# SCH_LFOx3_2024-04-05.net
KiCad netlist of a schematic drawn in EasyEDA
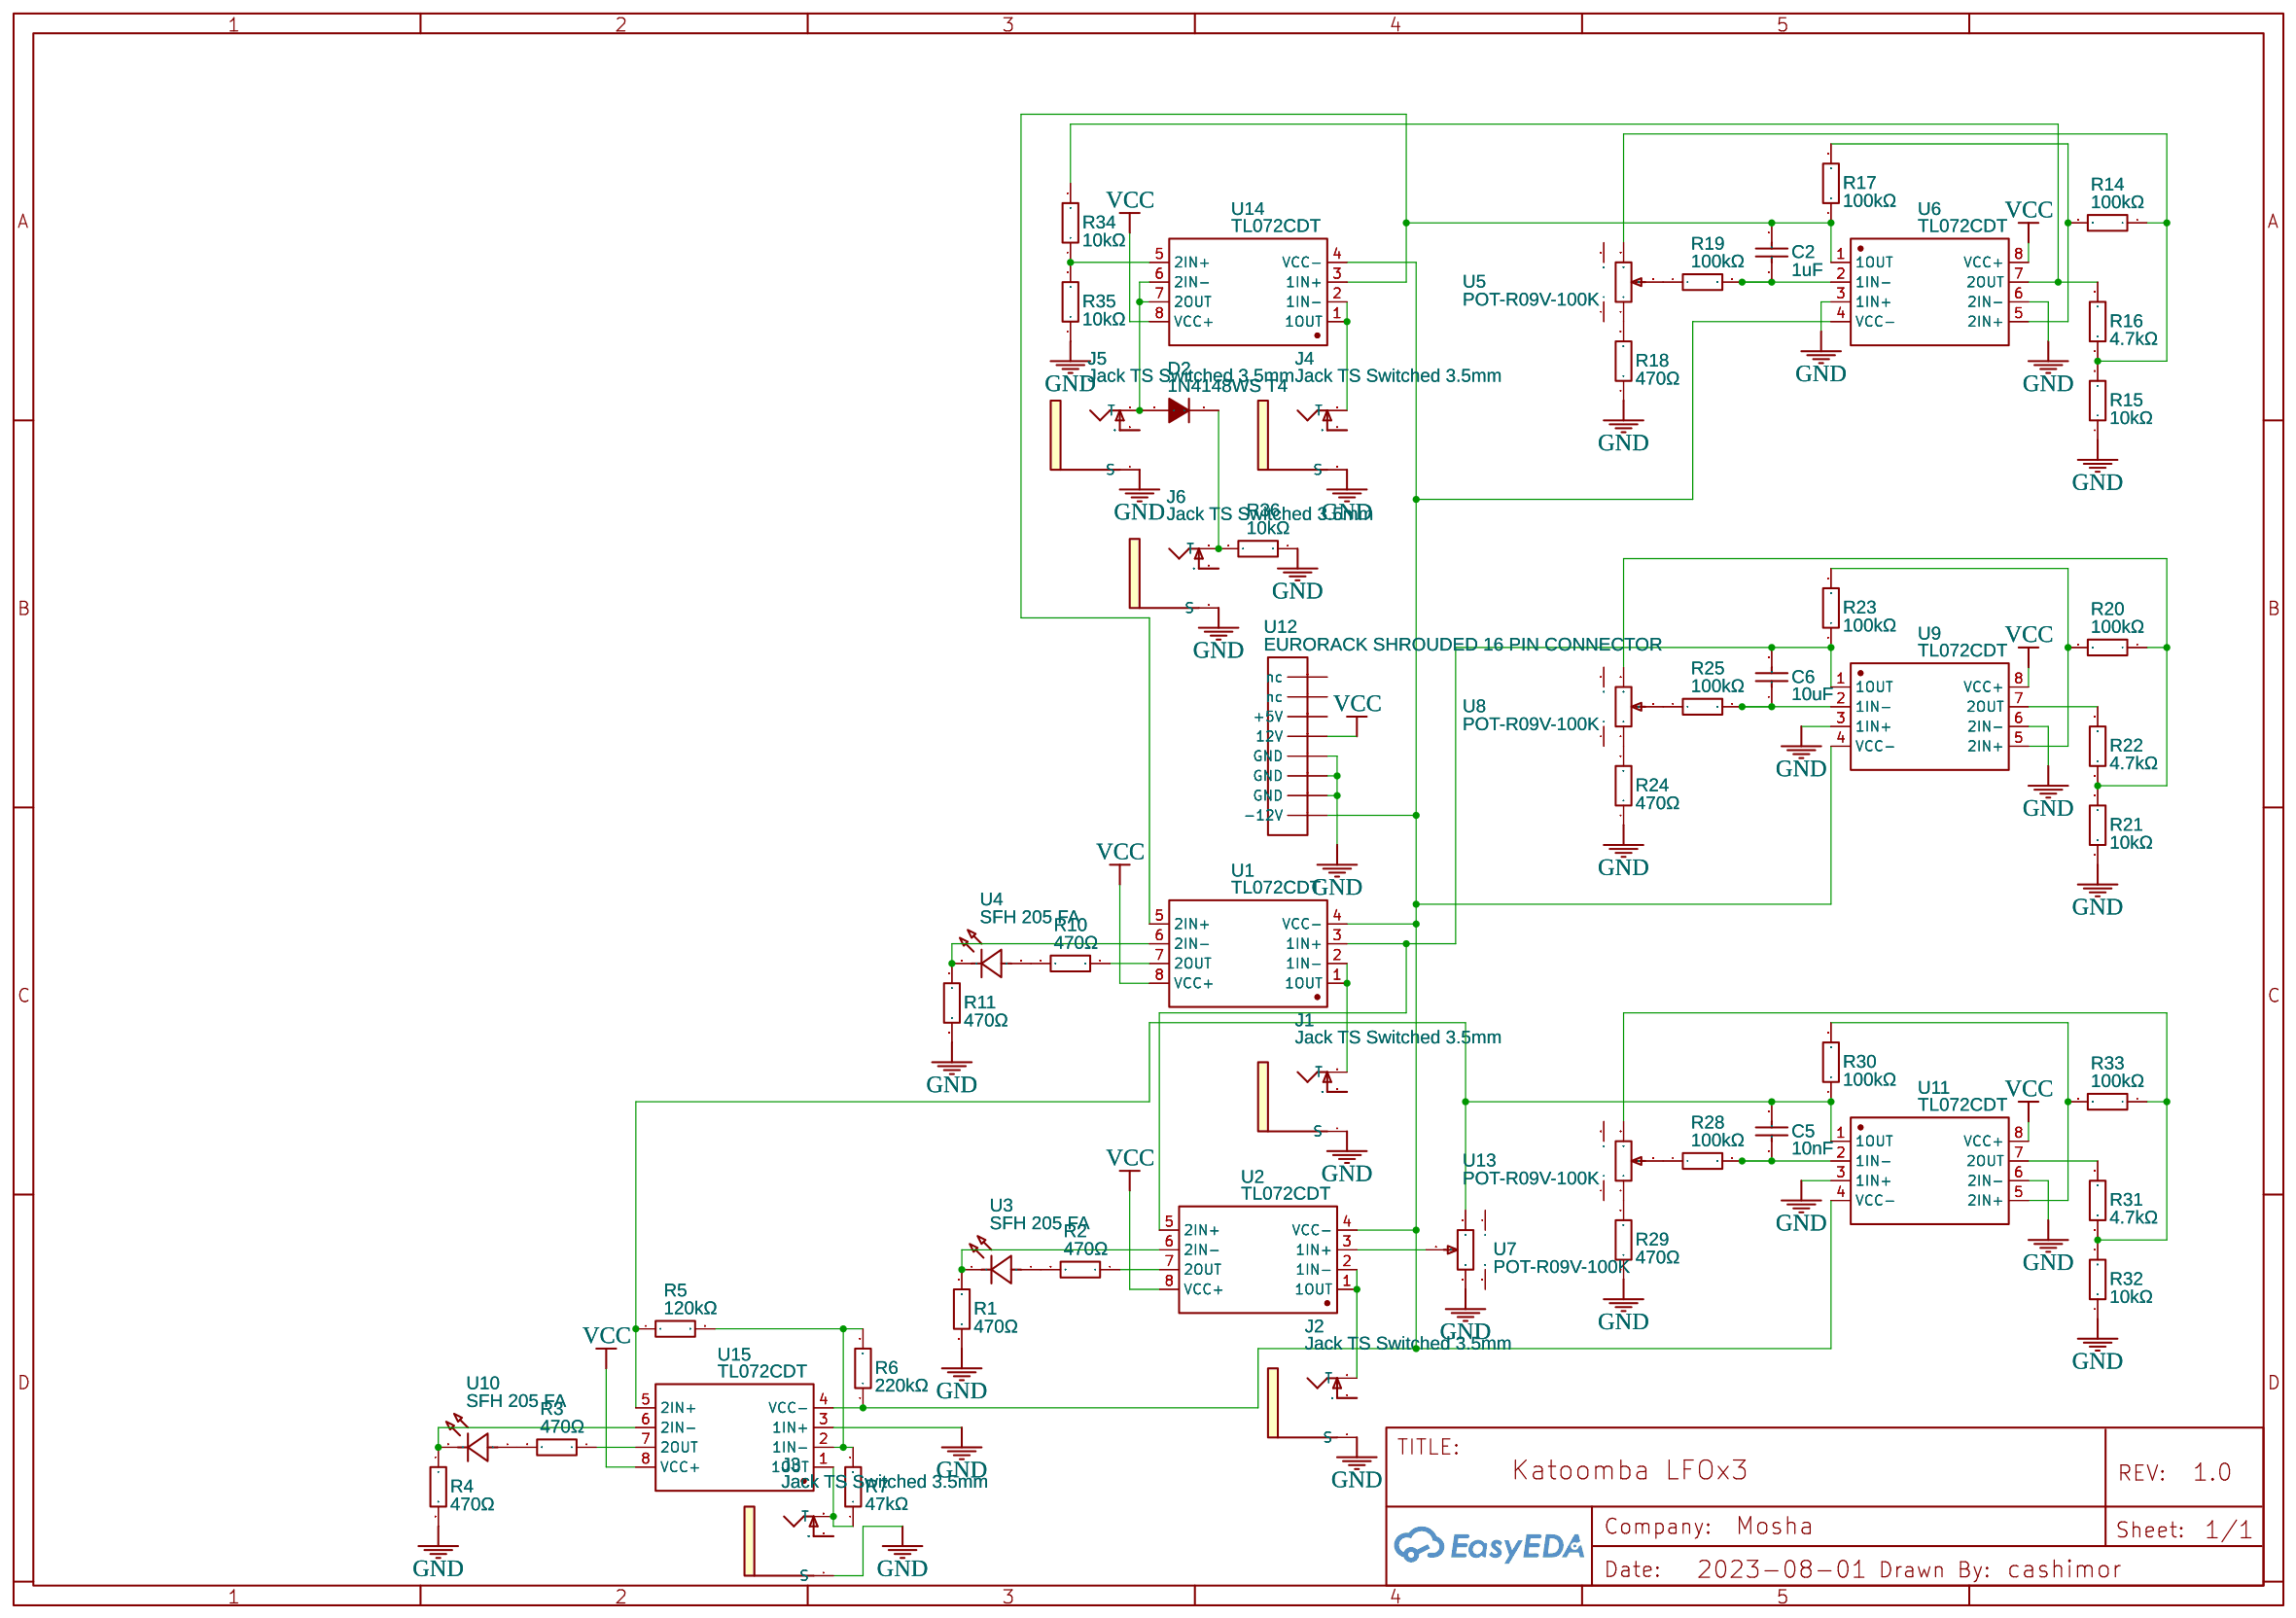
[diagram p0: schematic sheet]

(export (version "E")
  (design (tool "Eeschema 10.0.6"))
  (components
    (comp (ref "C2")
      (value "1uF")
      (fields
        (field (name "Manufacturer Part") "CL21B105KBFNNNE")
        (field (name "Manufacturer") "SAMSUNG(三星)")
      )
      (libsource (lib "") (part "CL21B105KBFNNNE"))
    )
    (comp (ref "C5")
      (value "10nF")
      (fields (field (name "Manufacturer Part") "0603B103K500NT") (field (name "Manufacturer") "FH(风华)"))
      (libsource (lib "") (part "0603B103K500NT"))
    )
    (comp (ref "C6")
      (value "10uF")
      (fields
        (field (name "Manufacturer Part") "CL21A106KAYNNNE")
        (field (name "Manufacturer") "SAMSUNG(三星)")
      )
      (libsource (lib "") (part "CL21A106KAYNNNE"))
    )
    (comp (ref "D2")
      (value "1N4148WS T4")
      (fields (field (name "Manufacturer Part") "1N4148WS") (field (name "Manufacturer") "CJ(江苏长电/长晶)"))
      (libsource (lib "") (part "1N4148WS T4"))
    )
    (comp (ref "J1") (value "Jack TS Switched 3.5mm") (libsource (lib "") (part "Jack TS Switched 3.5mm")))
    (comp (ref "J2") (value "Jack TS Switched 3.5mm") (libsource (lib "") (part "Jack TS Switched 3.5mm")))
    (comp (ref "J3") (value "Jack TS Switched 3.5mm") (libsource (lib "") (part "Jack TS Switched 3.5mm")))
    (comp (ref "J4") (value "Jack TS Switched 3.5mm") (libsource (lib "") (part "Jack TS Switched 3.5mm")))
    (comp (ref "J5") (value "Jack TS Switched 3.5mm") (libsource (lib "") (part "Jack TS Switched 3.5mm")))
    (comp (ref "J6") (value "Jack TS Switched 3.5mm") (libsource (lib "") (part "Jack TS Switched 3.5mm")))
    (comp (ref "R1")
      (value "470Ω")
      (fields
        (field (name "Manufacturer Part") "0805W8F4700T5E")
        (field (name "Manufacturer") "UNI-ROYAL(厚声)")
      )
      (libsource (lib "") (part "0805W8F4700T5E_1"))
    )
    (comp (ref "R2")
      (value "470Ω")
      (fields
        (field (name "Manufacturer Part") "0805W8F4700T5E")
        (field (name "Manufacturer") "UNI-ROYAL(厚声)")
      )
      (libsource (lib "") (part "0805W8F4700T5E_2"))
    )
    (comp (ref "R3")
      (value "470Ω")
      (fields
        (field (name "Manufacturer Part") "0805W8F4700T5E")
        (field (name "Manufacturer") "UNI-ROYAL(厚声)")
      )
      (libsource (lib "") (part "0805W8F4700T5E_2"))
    )
    (comp (ref "R4")
      (value "470Ω")
      (fields
        (field (name "Manufacturer Part") "0805W8F4700T5E")
        (field (name "Manufacturer") "UNI-ROYAL(厚声)")
      )
      (libsource (lib "") (part "0805W8F4700T5E_1"))
    )
    (comp (ref "R5")
      (value "120kΩ")
      (fields
        (field (name "Manufacturer Part") "0805W8F1203T5E")
        (field (name "Manufacturer") "UNI-ROYAL(厚声)")
      )
      (libsource (lib "") (part "0805W8F1203T5E"))
    )
    (comp (ref "R6")
      (value "220kΩ")
      (fields
        (field (name "Manufacturer Part") "0603WAF2203T5E")
        (field (name "Manufacturer") "UNI-ROYAL(厚声)")
      )
      (libsource (lib "") (part "0603WAF2203T5E"))
    )
    (comp (ref "R7")
      (value "47kΩ")
      (fields
        (field (name "Manufacturer Part") "0805W8F4702T5E")
        (field (name "Manufacturer") "UNI-ROYAL(厚声)")
      )
      (libsource (lib "") (part "0805W8F4702T5E"))
    )
    (comp (ref "R10")
      (value "470Ω")
      (fields
        (field (name "Manufacturer Part") "0805W8F4700T5E")
        (field (name "Manufacturer") "UNI-ROYAL(厚声)")
      )
      (libsource (lib "") (part "0805W8F4700T5E_2"))
    )
    (comp (ref "R11")
      (value "470Ω")
      (fields
        (field (name "Manufacturer Part") "0805W8F4700T5E")
        (field (name "Manufacturer") "UNI-ROYAL(厚声)")
      )
      (libsource (lib "") (part "0805W8F4700T5E_1"))
    )
    (comp (ref "R14")
      (value "100kΩ")
      (fields
        (field (name "Manufacturer Part") "0402WGF1003TCE")
        (field (name "Manufacturer") "UNI-ROYAL(厚声)")
      )
      (libsource (lib "") (part "0402WGF1003TCE_1"))
    )
    (comp (ref "R15")
      (value "10kΩ")
      (fields
        (field (name "Manufacturer Part") "0603WAF1002T5E")
        (field (name "Manufacturer") "UNI-ROYAL(厚声)")
      )
      (libsource (lib "") (part "0603WAF1002T5E"))
    )
    (comp (ref "R16")
      (value "4.7kΩ")
      (fields
        (field (name "Manufacturer Part") "1206W4F4701T5E")
        (field (name "Manufacturer") "UNI-ROYAL(厚声)")
      )
      (libsource (lib "") (part "1206W4F4701T5E"))
    )
    (comp (ref "R17")
      (value "100kΩ")
      (fields
        (field (name "Manufacturer Part") "0402WGF1003TCE")
        (field (name "Manufacturer") "UNI-ROYAL(厚声)")
      )
      (libsource (lib "") (part "0402WGF1003TCE"))
    )
    (comp (ref "R18")
      (value "470Ω")
      (fields
        (field (name "Manufacturer Part") "0805W8F4700T5E")
        (field (name "Manufacturer") "UNI-ROYAL(厚声)")
      )
      (libsource (lib "") (part "0805W8F4700T5E"))
    )
    (comp (ref "R19")
      (value "100kΩ")
      (fields
        (field (name "Manufacturer Part") "0402WGF1003TCE")
        (field (name "Manufacturer") "UNI-ROYAL(厚声)")
      )
      (libsource (lib "") (part "0402WGF1003TCE_2"))
    )
    (comp (ref "R20")
      (value "100kΩ")
      (fields
        (field (name "Manufacturer Part") "0402WGF1003TCE")
        (field (name "Manufacturer") "UNI-ROYAL(厚声)")
      )
      (libsource (lib "") (part "0402WGF1003TCE_1"))
    )
    (comp (ref "R21")
      (value "10kΩ")
      (fields
        (field (name "Manufacturer Part") "0603WAF1002T5E")
        (field (name "Manufacturer") "UNI-ROYAL(厚声)")
      )
      (libsource (lib "") (part "0603WAF1002T5E"))
    )
    (comp (ref "R22")
      (value "4.7kΩ")
      (fields
        (field (name "Manufacturer Part") "1206W4F4701T5E")
        (field (name "Manufacturer") "UNI-ROYAL(厚声)")
      )
      (libsource (lib "") (part "1206W4F4701T5E"))
    )
    (comp (ref "R23")
      (value "100kΩ")
      (fields
        (field (name "Manufacturer Part") "0402WGF1003TCE")
        (field (name "Manufacturer") "UNI-ROYAL(厚声)")
      )
      (libsource (lib "") (part "0402WGF1003TCE"))
    )
    (comp (ref "R24")
      (value "470Ω")
      (fields
        (field (name "Manufacturer Part") "0805W8F4700T5E")
        (field (name "Manufacturer") "UNI-ROYAL(厚声)")
      )
      (libsource (lib "") (part "0805W8F4700T5E"))
    )
    (comp (ref "R25")
      (value "100kΩ")
      (fields
        (field (name "Manufacturer Part") "0402WGF1003TCE")
        (field (name "Manufacturer") "UNI-ROYAL(厚声)")
      )
      (libsource (lib "") (part "0402WGF1003TCE_2"))
    )
    (comp (ref "R28")
      (value "100kΩ")
      (fields
        (field (name "Manufacturer Part") "0402WGF1003TCE")
        (field (name "Manufacturer") "UNI-ROYAL(厚声)")
      )
      (libsource (lib "") (part "0402WGF1003TCE_2"))
    )
    (comp (ref "R29")
      (value "470Ω")
      (fields
        (field (name "Manufacturer Part") "0805W8F4700T5E")
        (field (name "Manufacturer") "UNI-ROYAL(厚声)")
      )
      (libsource (lib "") (part "0805W8F4700T5E"))
    )
    (comp (ref "R30")
      (value "100kΩ")
      (fields
        (field (name "Manufacturer Part") "0402WGF1003TCE")
        (field (name "Manufacturer") "UNI-ROYAL(厚声)")
      )
      (libsource (lib "") (part "0402WGF1003TCE"))
    )
    (comp (ref "R31")
      (value "4.7kΩ")
      (fields
        (field (name "Manufacturer Part") "1206W4F4701T5E")
        (field (name "Manufacturer") "UNI-ROYAL(厚声)")
      )
      (libsource (lib "") (part "1206W4F4701T5E"))
    )
    (comp (ref "R32")
      (value "10kΩ")
      (fields
        (field (name "Manufacturer Part") "0603WAF1002T5E")
        (field (name "Manufacturer") "UNI-ROYAL(厚声)")
      )
      (libsource (lib "") (part "0603WAF1002T5E"))
    )
    (comp (ref "R33")
      (value "100kΩ")
      (fields
        (field (name "Manufacturer Part") "0402WGF1003TCE")
        (field (name "Manufacturer") "UNI-ROYAL(厚声)")
      )
      (libsource (lib "") (part "0402WGF1003TCE_1"))
    )
    (comp (ref "R34")
      (value "10kΩ")
      (fields
        (field (name "Manufacturer Part") "0603WAF1002T5E")
        (field (name "Manufacturer") "UNI-ROYAL(厚声)")
      )
      (libsource (lib "") (part "0603WAF1002T5E"))
    )
    (comp (ref "R35")
      (value "10kΩ")
      (fields
        (field (name "Manufacturer Part") "0603WAF1002T5E")
        (field (name "Manufacturer") "UNI-ROYAL(厚声)")
      )
      (libsource (lib "") (part "0603WAF1002T5E"))
    )
    (comp (ref "R36")
      (value "10kΩ")
      (fields
        (field (name "Manufacturer Part") "0603WAF1002T5E")
        (field (name "Manufacturer") "UNI-ROYAL(厚声)")
      )
      (libsource (lib "") (part "0603WAF1002T5E_1"))
    )
    (comp (ref "U1")
      (value "TL072CDT")
      (fields (field (name "Manufacturer") "ST(意法半导体)"))
      (libsource (lib "") (part "TL072CDT"))
    )
    (comp (ref "U2")
      (value "TL072CDT")
      (fields (field (name "Manufacturer") "ST(意法半导体)"))
      (libsource (lib "") (part "TL072CDT"))
    )
    (comp (ref "U3")
      (value "SFH 205 FA")
      (fields (field (name "Manufacturer") "OSRAM(欧司朗)"))
      (libsource (lib "") (part "SFH 205 FA"))
    )
    (comp (ref "U4")
      (value "SFH 205 FA")
      (fields (field (name "Manufacturer") "OSRAM(欧司朗)"))
      (libsource (lib "") (part "SFH 205 FA"))
    )
    (comp (ref "U5") (value "POT-R09V-100K") (libsource (lib "") (part "POT-R09V-100K")))
    (comp (ref "U6")
      (value "TL072CDT")
      (fields (field (name "Manufacturer") "ST(意法半导体)"))
      (libsource (lib "") (part "TL072CDT_1"))
    )
    (comp (ref "U7") (value "POT-R09V-100K") (libsource (lib "") (part "POT-R09V-100K_1")))
    (comp (ref "U8") (value "POT-R09V-100K") (libsource (lib "") (part "POT-R09V-100K")))
    (comp (ref "U9")
      (value "TL072CDT")
      (fields (field (name "Manufacturer") "ST(意法半导体)"))
      (libsource (lib "") (part "TL072CDT_1"))
    )
    (comp (ref "U10")
      (value "SFH 205 FA")
      (fields (field (name "Manufacturer") "OSRAM(欧司朗)"))
      (libsource (lib "") (part "SFH 205 FA"))
    )
    (comp (ref "U11")
      (value "TL072CDT")
      (fields (field (name "Manufacturer") "ST(意法半导体)"))
      (libsource (lib "") (part "TL072CDT_1"))
    )
    (comp (ref "U12")
      (value "EURORACK SHROUDED 16 PIN CONNECTOR")
      (fields (field (name "Manufacturer Part") "New SchematicLib"))
      (libsource (lib "") (part "EURORACK SHROUDED 16 PIN CONNECTOR"))
    )
    (comp (ref "U13") (value "POT-R09V-100K") (libsource (lib "") (part "POT-R09V-100K")))
    (comp (ref "U14")
      (value "TL072CDT")
      (fields (field (name "Manufacturer") "ST(意法半导体)"))
      (libsource (lib "") (part "TL072CDT"))
    )
    (comp (ref "U15")
      (value "TL072CDT")
      (fields (field (name "Manufacturer") "ST(意法半导体)"))
      (libsource (lib "") (part "TL072CDT"))
    )
  )
  (nets
    (net (code "1") (name "GND") (class "Default")
      (node (ref "J1") (pin "1") (pinfunction "S_1") (pintype "unspecified"))
      (node (ref "J2") (pin "1") (pinfunction "S_1") (pintype "unspecified"))
      (node (ref "J3") (pin "1") (pinfunction "S_1") (pintype "unspecified"))
      (node (ref "J4") (pin "1") (pinfunction "S_1") (pintype "unspecified"))
      (node (ref "J5") (pin "1") (pinfunction "S_1") (pintype "unspecified"))
      (node (ref "J6") (pin "1") (pinfunction "S_1") (pintype "unspecified"))
      (node (ref "R1") (pin "2") (pinfunction "2_2") (pintype "input"))
      (node (ref "R11") (pin "2") (pinfunction "2_2") (pintype "input"))
      (node (ref "R15") (pin "1") (pinfunction "1_1") (pintype "input"))
      (node (ref "R18") (pin "1") (pinfunction "1_1") (pintype "input"))
      (node (ref "R21") (pin "1") (pinfunction "1_1") (pintype "input"))
      (node (ref "R24") (pin "1") (pinfunction "1_1") (pintype "input"))
      (node (ref "R29") (pin "1") (pinfunction "1_1") (pintype "input"))
      (node (ref "R32") (pin "1") (pinfunction "1_1") (pintype "input"))
      (node (ref "R35") (pin "1") (pinfunction "1_1") (pintype "input"))
      (node (ref "R36") (pin "1") (pinfunction "1_1") (pintype "input"))
      (node (ref "R4") (pin "2") (pinfunction "2_2") (pintype "input"))
      (node (ref "U11") (pin "3") (pinfunction "1IN+_3") (pintype "unspecified"))
      (node (ref "U11") (pin "6") (pinfunction "2IN-_6") (pintype "unspecified"))
      (node (ref "U12") (pin "2") (pinfunction "GND_2") (pintype "unspecified"))
      (node (ref "U12") (pin "3") (pinfunction "GND_3") (pintype "unspecified"))
      (node (ref "U12") (pin "4") (pinfunction "GND_4") (pintype "unspecified"))
      (node (ref "U15") (pin "3") (pinfunction "1IN+_3") (pintype "unspecified"))
      (node (ref "U6") (pin "3") (pinfunction "1IN+_3") (pintype "unspecified"))
      (node (ref "U6") (pin "6") (pinfunction "2IN-_6") (pintype "unspecified"))
      (node (ref "U7") (pin "3") (pinfunction "3_3") (pintype "input"))
      (node (ref "U9") (pin "3") (pinfunction "1IN+_3") (pintype "unspecified"))
      (node (ref "U9") (pin "6") (pinfunction "2IN-_6") (pintype "unspecified"))
    )
    (net (code "2") (name "Net-(D2-A)") (class "Default")
      (node (ref "D2") (pin "2") (pinfunction "A_2") (pintype "unspecified"))
      (node (ref "J5") (pin "3") (pinfunction "T_3") (pintype "unspecified"))
      (node (ref "U14") (pin "6") (pinfunction "2IN-_6") (pintype "unspecified"))
      (node (ref "U14") (pin "7") (pinfunction "2OUT_7") (pintype "unspecified"))
    )
    (net (code "3") (name "Net-(D2-K)") (class "Default")
      (node (ref "D2") (pin "1") (pinfunction "K_1") (pintype "unspecified"))
      (node (ref "J6") (pin "3") (pinfunction "T_3") (pintype "unspecified"))
      (node (ref "R36") (pin "2") (pinfunction "2_2") (pintype "input"))
    )
    (net (code "4") (name "Net-(J1-T)") (class "Default")
      (node (ref "J1") (pin "3") (pinfunction "T_3") (pintype "unspecified"))
      (node (ref "U1") (pin "1") (pinfunction "1OUT_1") (pintype "unspecified"))
      (node (ref "U1") (pin "2") (pinfunction "1IN-_2") (pintype "unspecified"))
    )
    (net (code "5") (name "Net-(J2-T)") (class "Default")
      (node (ref "J2") (pin "3") (pinfunction "T_3") (pintype "unspecified"))
      (node (ref "U2") (pin "1") (pinfunction "1OUT_1") (pintype "unspecified"))
      (node (ref "U2") (pin "2") (pinfunction "1IN-_2") (pintype "unspecified"))
    )
    (net (code "6") (name "Net-(J3-T)") (class "Default")
      (node (ref "J3") (pin "3") (pinfunction "T_3") (pintype "unspecified"))
      (node (ref "R7") (pin "1") (pinfunction "1_1") (pintype "input"))
      (node (ref "U15") (pin "1") (pinfunction "1OUT_1") (pintype "unspecified"))
    )
    (net (code "7") (name "Net-(J4-T)") (class "Default")
      (node (ref "J4") (pin "3") (pinfunction "T_3") (pintype "unspecified"))
      (node (ref "U14") (pin "1") (pinfunction "1OUT_1") (pintype "unspecified"))
      (node (ref "U14") (pin "2") (pinfunction "1IN-_2") (pintype "unspecified"))
    )
    (net (code "8") (name "Net-(R14-Pad1)") (class "Default")
      (node (ref "R14") (pin "1") (pinfunction "1_1") (pintype "input"))
      (node (ref "R15") (pin "2") (pinfunction "2_2") (pintype "input"))
      (node (ref "R16") (pin "1") (pinfunction "1_1") (pintype "input"))
      (node (ref "U5") (pin "3") (pinfunction "3_3") (pintype "input"))
    )
    (net (code "9") (name "Net-(R18-Pad2)") (class "Default")
      (node (ref "R18") (pin "2") (pinfunction "2_2") (pintype "input"))
      (node (ref "U5") (pin "1") (pinfunction "1_1") (pintype "input"))
    )
    (net (code "10") (name "Net-(R19-Pad1)") (class "Default")
      (node (ref "R19") (pin "1") (pinfunction "1_1") (pintype "input"))
      (node (ref "U5") (pin "2") (pinfunction "2_2") (pintype "input"))
    )
    (net (code "11") (name "Net-(R20-Pad1)") (class "Default")
      (node (ref "R20") (pin "1") (pinfunction "1_1") (pintype "input"))
      (node (ref "R21") (pin "2") (pinfunction "2_2") (pintype "input"))
      (node (ref "R22") (pin "1") (pinfunction "1_1") (pintype "input"))
      (node (ref "U8") (pin "3") (pinfunction "3_3") (pintype "input"))
    )
    (net (code "12") (name "Net-(R24-Pad2)") (class "Default")
      (node (ref "R24") (pin "2") (pinfunction "2_2") (pintype "input"))
      (node (ref "U8") (pin "1") (pinfunction "1_1") (pintype "input"))
    )
    (net (code "13") (name "Net-(R25-Pad1)") (class "Default")
      (node (ref "R25") (pin "1") (pinfunction "1_1") (pintype "input"))
      (node (ref "U8") (pin "2") (pinfunction "2_2") (pintype "input"))
    )
    (net (code "14") (name "Net-(R28-Pad1)") (class "Default")
      (node (ref "R28") (pin "1") (pinfunction "1_1") (pintype "input"))
      (node (ref "U13") (pin "2") (pinfunction "2_2") (pintype "input"))
    )
    (net (code "15") (name "Net-(R29-Pad2)") (class "Default")
      (node (ref "R29") (pin "2") (pinfunction "2_2") (pintype "input"))
      (node (ref "U13") (pin "1") (pinfunction "1_1") (pintype "input"))
    )
    (net (code "16") (name "Net-(R31-Pad1)") (class "Default")
      (node (ref "R31") (pin "1") (pinfunction "1_1") (pintype "input"))
      (node (ref "R32") (pin "2") (pinfunction "2_2") (pintype "input"))
      (node (ref "R33") (pin "1") (pinfunction "1_1") (pintype "input"))
      (node (ref "U13") (pin "3") (pinfunction "3_3") (pintype "input"))
    )
    (net (code "17") (name "Net-(U1-1IN+)") (class "Default")
      (node (ref "C6") (pin "2") (pinfunction "2_2") (pintype "input"))
      (node (ref "R23") (pin "1") (pinfunction "1_1") (pintype "input"))
      (node (ref "U1") (pin "3") (pinfunction "1IN+_3") (pintype "unspecified"))
      (node (ref "U2") (pin "5") (pinfunction "2IN+_5") (pintype "unspecified"))
      (node (ref "U9") (pin "1") (pinfunction "1OUT_1") (pintype "unspecified"))
    )
    (net (code "18") (name "Net-(U1-2IN+)") (class "Default")
      (node (ref "C2") (pin "2") (pinfunction "2_2") (pintype "input"))
      (node (ref "R17") (pin "1") (pinfunction "1_1") (pintype "input"))
      (node (ref "U1") (pin "5") (pinfunction "2IN+_5") (pintype "unspecified"))
      (node (ref "U14") (pin "3") (pinfunction "1IN+_3") (pintype "unspecified"))
      (node (ref "U6") (pin "1") (pinfunction "1OUT_1") (pintype "unspecified"))
    )
    (net (code "19") (name "Net-(U1-2IN-)") (class "Default")
      (node (ref "R11") (pin "1") (pinfunction "1_1") (pintype "input"))
      (node (ref "U1") (pin "6") (pinfunction "2IN-_6") (pintype "unspecified"))
      (node (ref "U4") (pin "2") (pinfunction "K_2") (pintype "unspecified"))
    )
    (net (code "20") (name "Net-(U1-2OUT)") (class "Default")
      (node (ref "R10") (pin "1") (pinfunction "1_1") (pintype "input"))
      (node (ref "U1") (pin "7") (pinfunction "2OUT_7") (pintype "unspecified"))
    )
    (net (code "21") (name "Net-(U1-VCC-)") (class "Default")
      (node (ref "R6") (pin "1") (pinfunction "1_1") (pintype "input"))
      (node (ref "U1") (pin "4") (pinfunction "VCC-_4") (pintype "unspecified"))
      (node (ref "U11") (pin "4") (pinfunction "VCC-_4") (pintype "unspecified"))
      (node (ref "U12") (pin "1") (pinfunction "-12V_1") (pintype "unspecified"))
      (node (ref "U14") (pin "4") (pinfunction "VCC-_4") (pintype "unspecified"))
      (node (ref "U15") (pin "4") (pinfunction "VCC-_4") (pintype "unspecified"))
      (node (ref "U2") (pin "4") (pinfunction "VCC-_4") (pintype "unspecified"))
      (node (ref "U6") (pin "4") (pinfunction "VCC-_4") (pintype "unspecified"))
      (node (ref "U9") (pin "4") (pinfunction "VCC-_4") (pintype "unspecified"))
    )
    (net (code "22") (name "Net-(U2-1IN+)") (class "Default")
      (node (ref "U2") (pin "3") (pinfunction "1IN+_3") (pintype "unspecified"))
      (node (ref "U7") (pin "2") (pinfunction "2_2") (pintype "input"))
    )
    (net (code "23") (name "Net-(U2-2IN-)") (class "Default")
      (node (ref "R1") (pin "1") (pinfunction "1_1") (pintype "input"))
      (node (ref "U2") (pin "6") (pinfunction "2IN-_6") (pintype "unspecified"))
      (node (ref "U3") (pin "2") (pinfunction "K_2") (pintype "unspecified"))
    )
    (net (code "24") (name "Net-(U2-2OUT)") (class "Default")
      (node (ref "R2") (pin "1") (pinfunction "1_1") (pintype "input"))
      (node (ref "U2") (pin "7") (pinfunction "2OUT_7") (pintype "unspecified"))
    )
    (net (code "25") (name "Net-(U3-A)") (class "Default")
      (node (ref "R2") (pin "2") (pinfunction "2_2") (pintype "input"))
      (node (ref "U3") (pin "1") (pinfunction "A_1") (pintype "unspecified"))
    )
    (net (code "26") (name "Net-(U4-A)") (class "Default")
      (node (ref "R10") (pin "2") (pinfunction "2_2") (pintype "input"))
      (node (ref "U4") (pin "1") (pinfunction "A_1") (pintype "unspecified"))
    )
    (net (code "27") (name "Net-(U6-1IN-)") (class "Default")
      (node (ref "C2") (pin "1") (pinfunction "1_1") (pintype "input"))
      (node (ref "R19") (pin "2") (pinfunction "2_2") (pintype "input"))
      (node (ref "U6") (pin "2") (pinfunction "1IN-_2") (pintype "unspecified"))
    )
    (net (code "28") (name "Net-(U6-2IN+)") (class "Default")
      (node (ref "R14") (pin "2") (pinfunction "2_2") (pintype "input"))
      (node (ref "R17") (pin "2") (pinfunction "2_2") (pintype "input"))
      (node (ref "U6") (pin "5") (pinfunction "2IN+_5") (pintype "unspecified"))
    )
    (net (code "29") (name "Net-(U6-2OUT)") (class "Default")
      (node (ref "R16") (pin "2") (pinfunction "2_2") (pintype "input"))
      (node (ref "R34") (pin "2") (pinfunction "2_2") (pintype "input"))
      (node (ref "U6") (pin "7") (pinfunction "2OUT_7") (pintype "unspecified"))
    )
    (net (code "30") (name "Net-(U9-1IN-)") (class "Default")
      (node (ref "C6") (pin "1") (pinfunction "1_1") (pintype "input"))
      (node (ref "R25") (pin "2") (pinfunction "2_2") (pintype "input"))
      (node (ref "U9") (pin "2") (pinfunction "1IN-_2") (pintype "unspecified"))
    )
    (net (code "31") (name "Net-(U9-2IN+)") (class "Default")
      (node (ref "R20") (pin "2") (pinfunction "2_2") (pintype "input"))
      (node (ref "R23") (pin "2") (pinfunction "2_2") (pintype "input"))
      (node (ref "U9") (pin "5") (pinfunction "2IN+_5") (pintype "unspecified"))
    )
    (net (code "32") (name "Net-(U9-2OUT)") (class "Default")
      (node (ref "R22") (pin "2") (pinfunction "2_2") (pintype "input"))
      (node (ref "U9") (pin "7") (pinfunction "2OUT_7") (pintype "unspecified"))
    )
    (net (code "33") (name "Net-(U10-A)") (class "Default")
      (node (ref "R3") (pin "2") (pinfunction "2_2") (pintype "input"))
      (node (ref "U10") (pin "1") (pinfunction "A_1") (pintype "unspecified"))
    )
    (net (code "34") (name "Net-(U10-K)") (class "Default")
      (node (ref "R4") (pin "1") (pinfunction "1_1") (pintype "input"))
      (node (ref "U10") (pin "2") (pinfunction "K_2") (pintype "unspecified"))
      (node (ref "U15") (pin "6") (pinfunction "2IN-_6") (pintype "unspecified"))
    )
    (net (code "35") (name "Net-(U11-1IN-)") (class "Default")
      (node (ref "C5") (pin "1") (pinfunction "1_1") (pintype "input"))
      (node (ref "R28") (pin "2") (pinfunction "2_2") (pintype "input"))
      (node (ref "U11") (pin "2") (pinfunction "1IN-_2") (pintype "unspecified"))
    )
    (net (code "36") (name "Net-(U11-1OUT)") (class "Default")
      (node (ref "C5") (pin "2") (pinfunction "2_2") (pintype "input"))
      (node (ref "R30") (pin "1") (pinfunction "1_1") (pintype "input"))
      (node (ref "R5") (pin "1") (pinfunction "1_1") (pintype "input"))
      (node (ref "U11") (pin "1") (pinfunction "1OUT_1") (pintype "unspecified"))
      (node (ref "U15") (pin "5") (pinfunction "2IN+_5") (pintype "unspecified"))
      (node (ref "U7") (pin "1") (pinfunction "1_1") (pintype "input"))
    )
    (net (code "37") (name "Net-(U11-2IN+)") (class "Default")
      (node (ref "R30") (pin "2") (pinfunction "2_2") (pintype "input"))
      (node (ref "R33") (pin "2") (pinfunction "2_2") (pintype "input"))
      (node (ref "U11") (pin "5") (pinfunction "2IN+_5") (pintype "unspecified"))
    )
    (net (code "38") (name "Net-(U11-2OUT)") (class "Default")
      (node (ref "R31") (pin "2") (pinfunction "2_2") (pintype "input"))
      (node (ref "U11") (pin "7") (pinfunction "2OUT_7") (pintype "unspecified"))
    )
    (net (code "39") (name "Net-(U14-2IN+)") (class "Default")
      (node (ref "R34") (pin "1") (pinfunction "1_1") (pintype "input"))
      (node (ref "R35") (pin "2") (pinfunction "2_2") (pintype "input"))
      (node (ref "U14") (pin "5") (pinfunction "2IN+_5") (pintype "unspecified"))
    )
    (net (code "40") (name "Net-(U15-1IN-)") (class "Default")
      (node (ref "R5") (pin "2") (pinfunction "2_2") (pintype "input"))
      (node (ref "R6") (pin "2") (pinfunction "2_2") (pintype "input"))
      (node (ref "R7") (pin "2") (pinfunction "2_2") (pintype "input"))
      (node (ref "U15") (pin "2") (pinfunction "1IN-_2") (pintype "unspecified"))
    )
    (net (code "41") (name "Net-(U15-2OUT)") (class "Default")
      (node (ref "R3") (pin "1") (pinfunction "1_1") (pintype "input"))
      (node (ref "U15") (pin "7") (pinfunction "2OUT_7") (pintype "unspecified"))
    )
    (net (code "42") (name "VCC") (class "Default")
      (node (ref "U1") (pin "8") (pinfunction "VCC+_8") (pintype "unspecified"))
      (node (ref "U11") (pin "8") (pinfunction "VCC+_8") (pintype "unspecified"))
      (node (ref "U12") (pin "5") (pinfunction "12V_5") (pintype "unspecified"))
      (node (ref "U14") (pin "8") (pinfunction "VCC+_8") (pintype "unspecified"))
      (node (ref "U15") (pin "8") (pinfunction "VCC+_8") (pintype "unspecified"))
      (node (ref "U2") (pin "8") (pinfunction "VCC+_8") (pintype "unspecified"))
      (node (ref "U6") (pin "8") (pinfunction "VCC+_8") (pintype "unspecified"))
      (node (ref "U9") (pin "8") (pinfunction "VCC+_8") (pintype "unspecified"))
    )
    (net (code "43") (name "unconnected-(J1-Tsw-Pad2)") (class "Default")
      (node (ref "J1") (pin "2") (pinfunction "Tsw_2") (pintype "unspecified"))
    )
    (net (code "44") (name "unconnected-(J2-Tsw-Pad2)") (class "Default")
      (node (ref "J2") (pin "2") (pinfunction "Tsw_2") (pintype "unspecified"))
    )
    (net (code "45") (name "unconnected-(J3-Tsw-Pad2)") (class "Default")
      (node (ref "J3") (pin "2") (pinfunction "Tsw_2") (pintype "unspecified"))
    )
    (net (code "46") (name "unconnected-(J4-Tsw-Pad2)") (class "Default")
      (node (ref "J4") (pin "2") (pinfunction "Tsw_2") (pintype "unspecified"))
    )
    (net (code "47") (name "unconnected-(J5-Tsw-Pad2)") (class "Default")
      (node (ref "J5") (pin "2") (pinfunction "Tsw_2") (pintype "unspecified"))
    )
    (net (code "48") (name "unconnected-(J6-Tsw-Pad2)") (class "Default")
      (node (ref "J6") (pin "2") (pinfunction "Tsw_2") (pintype "unspecified"))
    )
    (net (code "49") (name "unconnected-(U5-Pad4)") (class "Default")
      (node (ref "U5") (pin "4") (pinfunction "4_4") (pintype "input"))
    )
    (net (code "50") (name "unconnected-(U5-Pad5)") (class "Default")
      (node (ref "U5") (pin "5") (pinfunction "5_5") (pintype "input"))
    )
    (net (code "51") (name "unconnected-(U7-Pad4)") (class "Default")
      (node (ref "U7") (pin "4") (pinfunction "4_4") (pintype "input"))
    )
    (net (code "52") (name "unconnected-(U7-Pad5)") (class "Default")
      (node (ref "U7") (pin "5") (pinfunction "5_5") (pintype "input"))
    )
    (net (code "53") (name "unconnected-(U8-Pad4)") (class "Default")
      (node (ref "U8") (pin "4") (pinfunction "4_4") (pintype "input"))
    )
    (net (code "54") (name "unconnected-(U8-Pad5)") (class "Default")
      (node (ref "U8") (pin "5") (pinfunction "5_5") (pintype "input"))
    )
    (net (code "55") (name "unconnected-(U12-+5V-Pad6)") (class "Default")
      (node (ref "U12") (pin "6") (pinfunction "+5V_6") (pintype "unspecified"))
    )
    (net (code "56") (name "unconnected-(U12-nc-Pad7)") (class "Default")
      (node (ref "U12") (pin "7") (pinfunction "nc_7") (pintype "unspecified"))
    )
    (net (code "57") (name "unconnected-(U12-nc-Pad8)") (class "Default")
      (node (ref "U12") (pin "8") (pinfunction "nc_8") (pintype "unspecified"))
    )
    (net (code "58") (name "unconnected-(U13-Pad4)") (class "Default")
      (node (ref "U13") (pin "4") (pinfunction "4_4") (pintype "input"))
    )
    (net (code "59") (name "unconnected-(U13-Pad5)") (class "Default")
      (node (ref "U13") (pin "5") (pinfunction "5_5") (pintype "input"))
    )
  )
)
